# ETH_SWITCH.net
KiCad netlist of a schematic drawn in Altium Designer
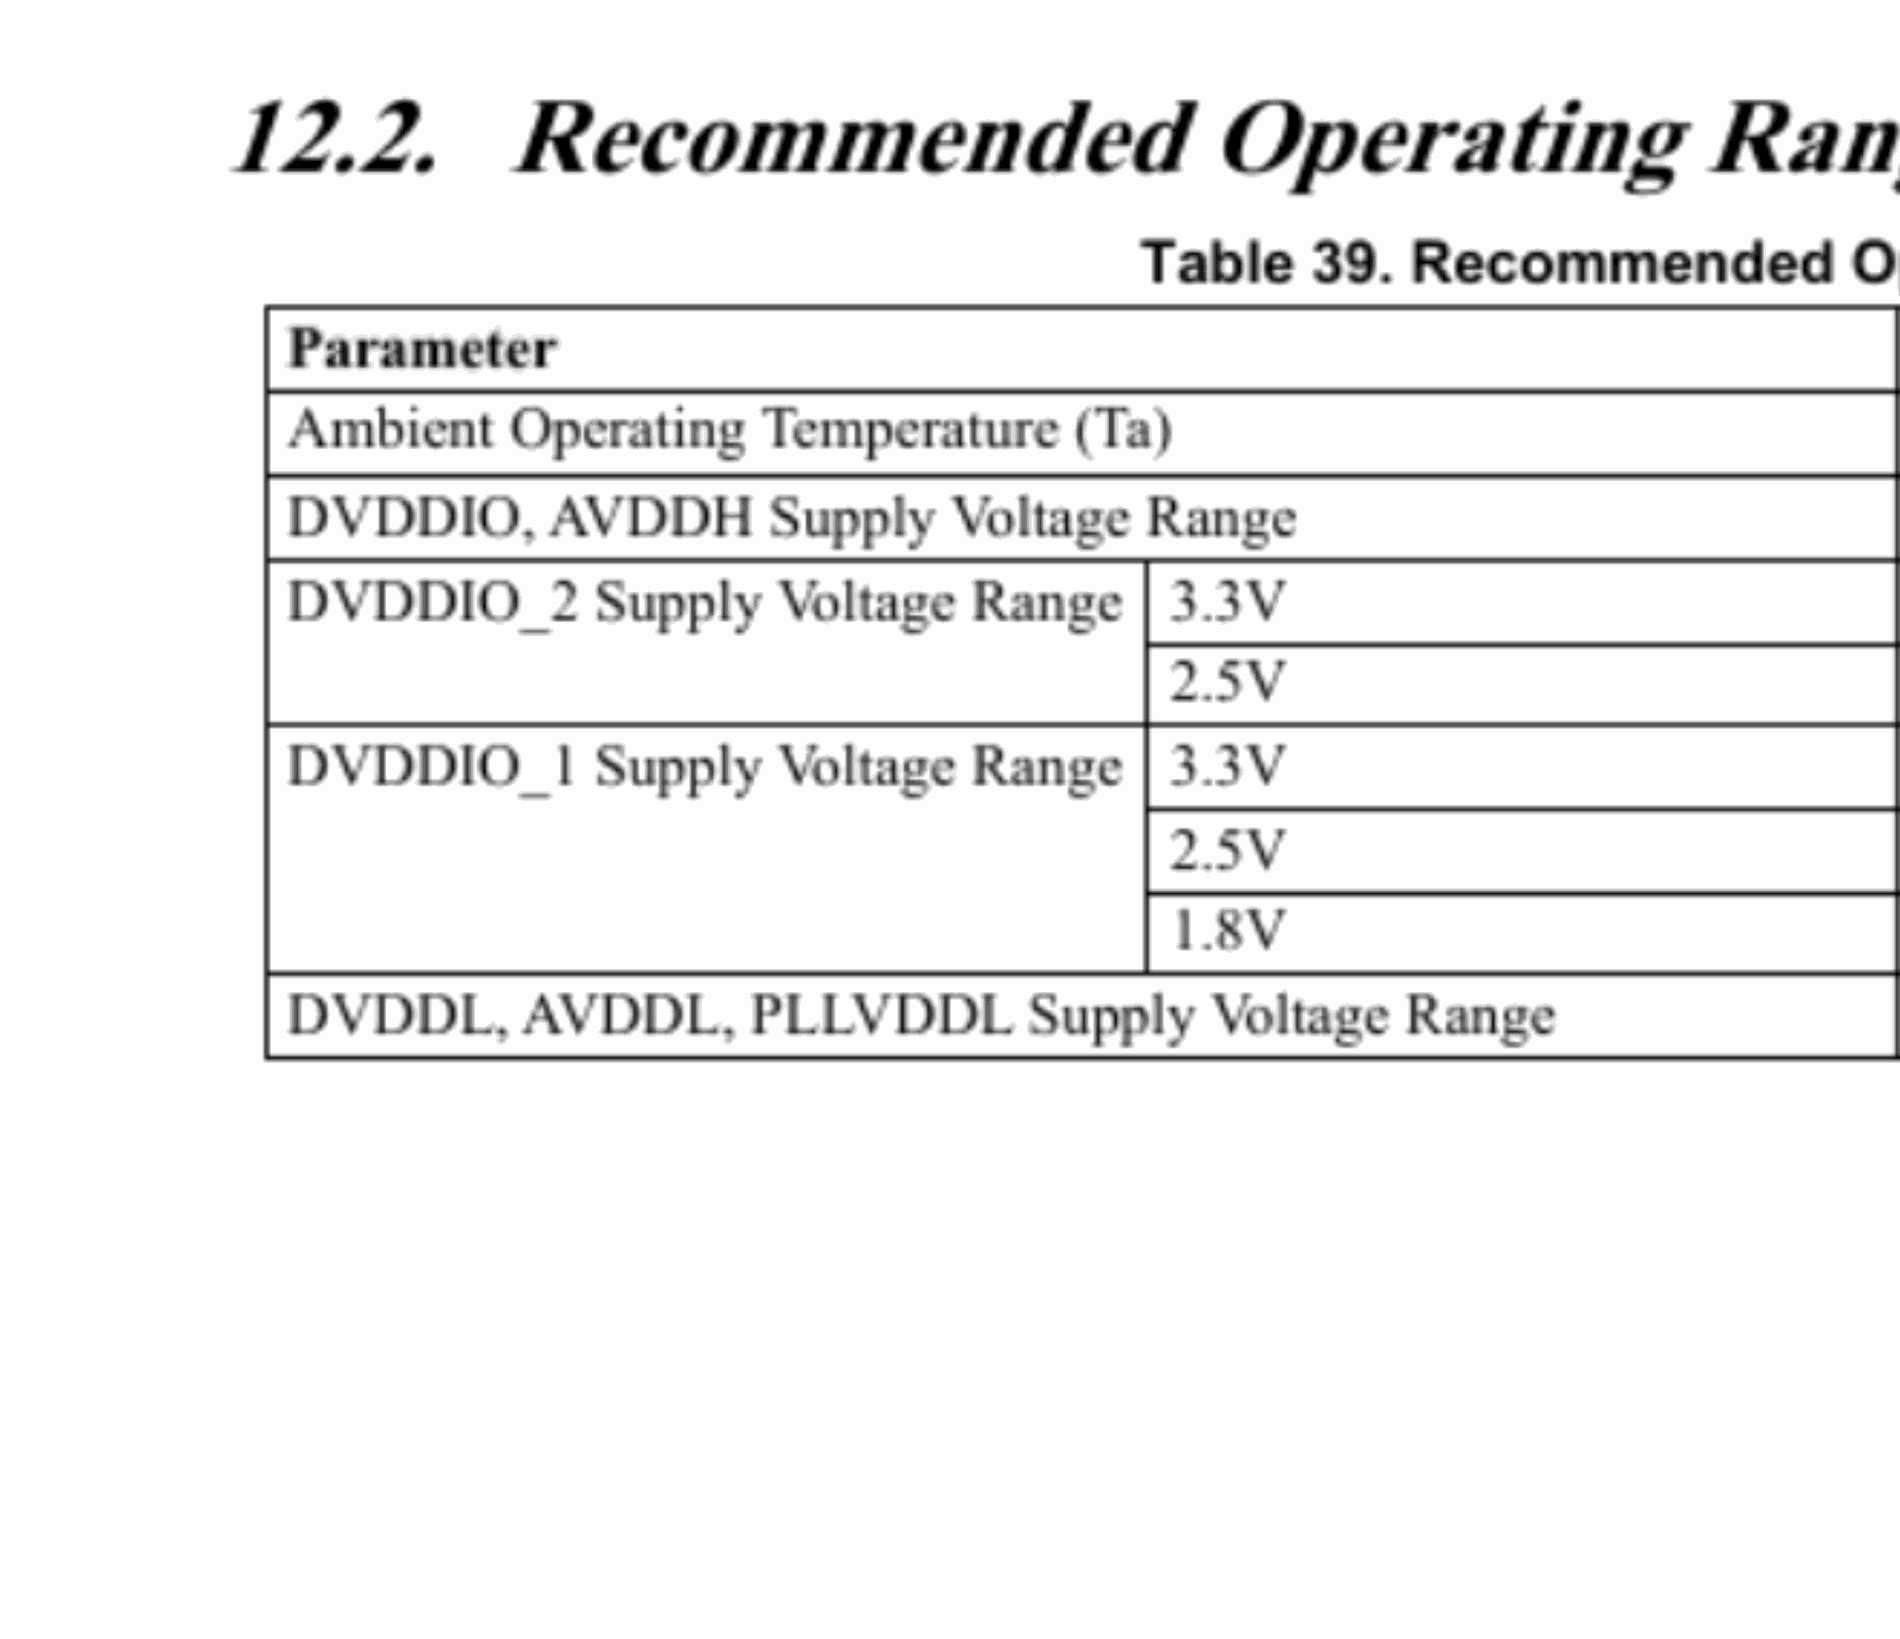
[diagram p0: ETH_SWITCH.SchDoc, top left]
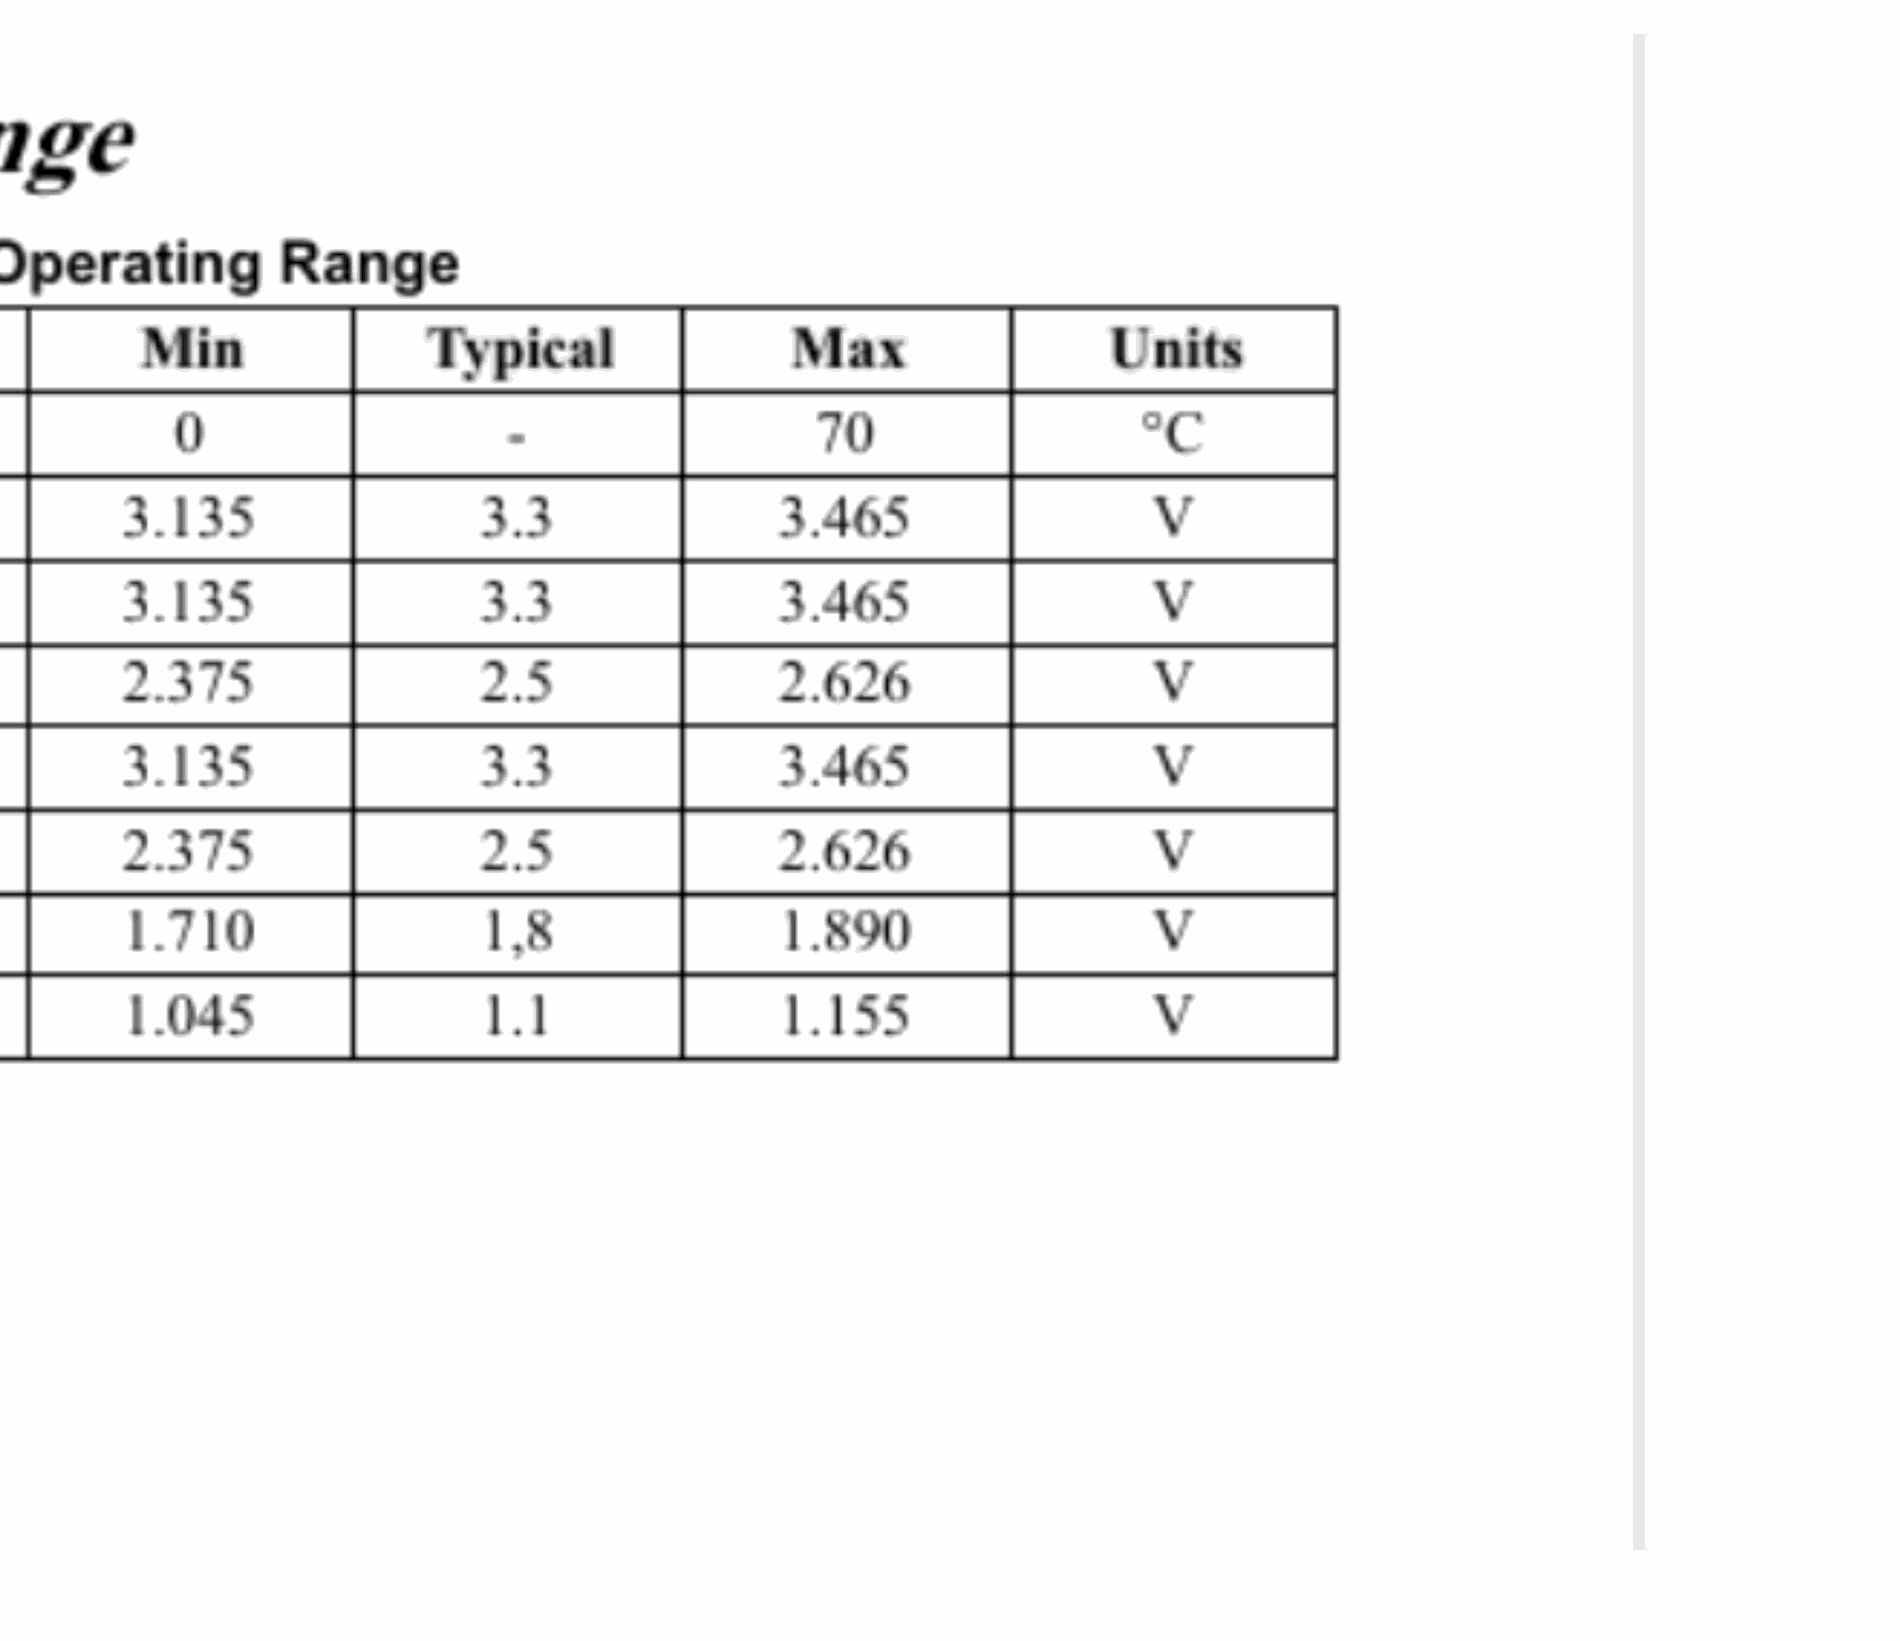
[diagram p1: ETH_SWITCH.SchDoc, top right]
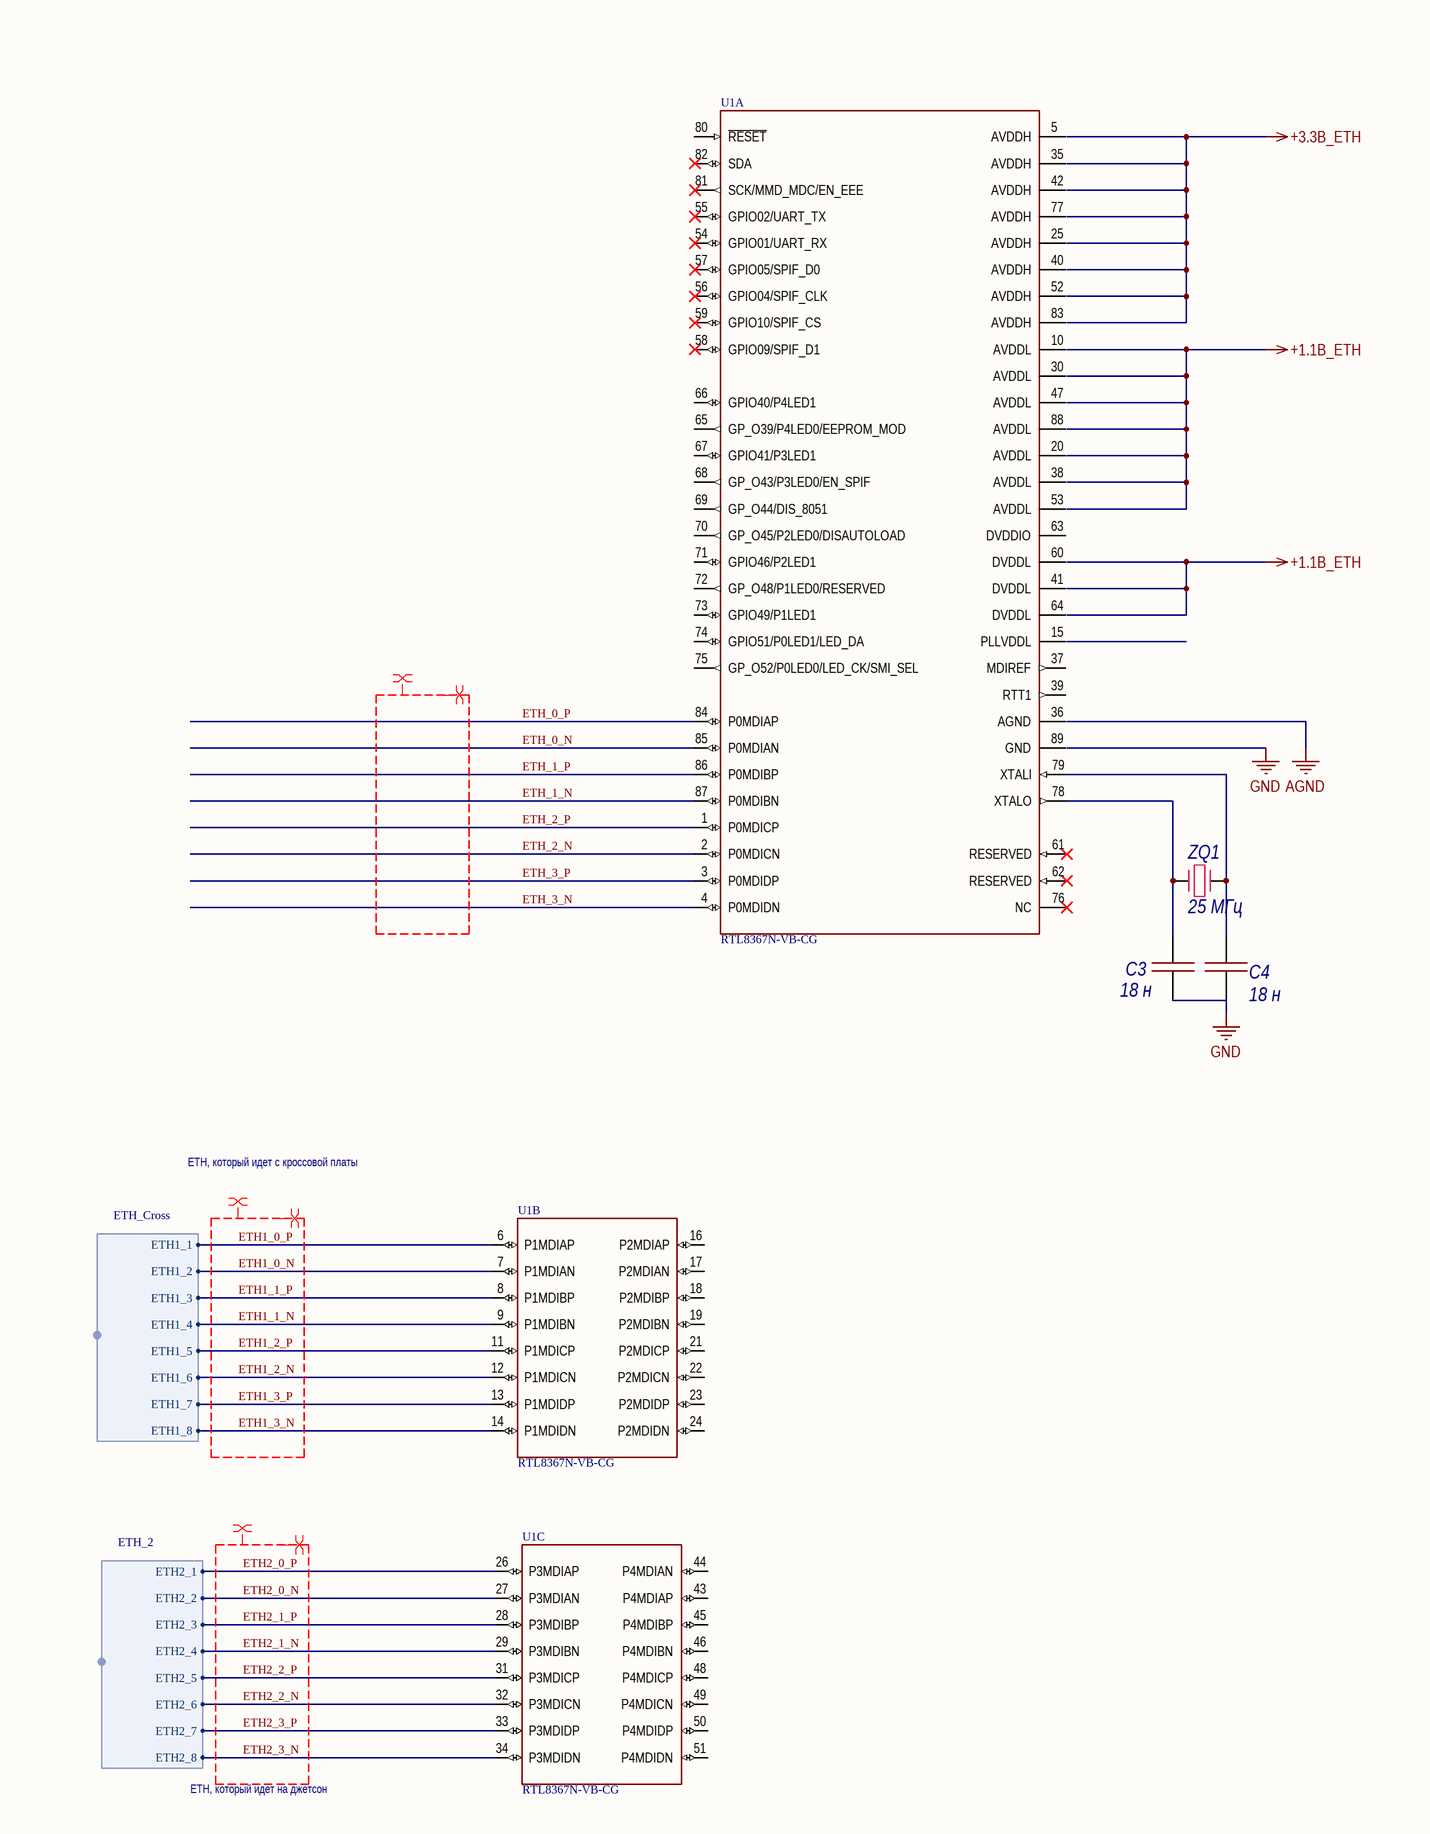
[diagram p2: ETH_SWITCH.SchDoc, bottom left]

(export (version "E")
  (design (tool "Eeschema 10.0.6"))
  (components
    (comp (ref "C3")
      (value "18 н")
      (footprint "0603C")
      (description "Конденсатор")
      (fields (field (name "PART NUMBER") "Capacitor_18n_10_50V_X7R_0603C") (field (name "TOLERANCE") "0,1"))
      (libsource (lib "Hydrolib") (part "Capacitor"))
    )
    (comp (ref "C4")
      (value "18 н")
      (footprint "0603C")
      (description "Конденсатор")
      (fields (field (name "PART NUMBER") "Capacitor_18n_10_50V_X7R_0603C") (field (name "TOLERANCE") "0,1"))
      (libsource (lib "Hydrolib") (part "Capacitor"))
    )
    (comp (ref "U1")
      (value "RTL8367N-VB-CG")
      (footprint "QFN40P1000X1000X90-89N")
      (fields (field (name "MF") "Realtek"))
      (libsource (lib "Hydrolib") (part "RTL8367N-VB-CG"))
    )
    (comp (ref "ZQ1")
      (value "25 МГц")
      (footprint "HC49SD")
      (description "Кварцевый резонатор")
      (fields (field (name "PART NUMBER") "XTAL"))
      (libsource (lib "Hydrolib") (part "XTAL"))
    )
  )
  (nets
    (net (code "3") (name "/ETH1_0_N") (class "Default")
      (node (ref "U1") (pin "7") (pinfunction "P1MDIAN_7") (pintype "bidirectional"))
    )
    (net (code "4") (name "/ETH1_0_P") (class "Default")
      (node (ref "U1") (pin "6") (pinfunction "P1MDIAP_6") (pintype "bidirectional"))
    )
    (net (code "5") (name "/ETH1_1_N") (class "Default")
      (node (ref "U1") (pin "9") (pinfunction "P1MDIBN_9") (pintype "bidirectional"))
    )
    (net (code "6") (name "/ETH1_1_P") (class "Default")
      (node (ref "U1") (pin "8") (pinfunction "P1MDIBP_8") (pintype "bidirectional"))
    )
    (net (code "7") (name "/ETH1_2_N") (class "Default")
      (node (ref "U1") (pin "12") (pinfunction "P1MDICN_12") (pintype "bidirectional"))
    )
    (net (code "8") (name "/ETH1_2_P") (class "Default")
      (node (ref "U1") (pin "11") (pinfunction "P1MDICP_11") (pintype "bidirectional"))
    )
    (net (code "9") (name "/ETH1_3_N") (class "Default")
      (node (ref "U1") (pin "14") (pinfunction "P1MDIDN_14") (pintype "bidirectional"))
    )
    (net (code "10") (name "/ETH1_3_P") (class "Default")
      (node (ref "U1") (pin "13") (pinfunction "P1MDIDP_13") (pintype "bidirectional"))
    )
    (net (code "11") (name "/ETH2_0_N") (class "Default")
      (node (ref "U1") (pin "27") (pinfunction "P3MDIAN_27") (pintype "bidirectional"))
    )
    (net (code "12") (name "/ETH2_0_P") (class "Default")
      (node (ref "U1") (pin "26") (pinfunction "P3MDIAP_26") (pintype "bidirectional"))
    )
    (net (code "13") (name "/ETH2_1_N") (class "Default")
      (node (ref "U1") (pin "29") (pinfunction "P3MDIBN_29") (pintype "bidirectional"))
    )
    (net (code "14") (name "/ETH2_1_P") (class "Default")
      (node (ref "U1") (pin "28") (pinfunction "P3MDIBP_28") (pintype "bidirectional"))
    )
    (net (code "15") (name "/ETH2_2_N") (class "Default")
      (node (ref "U1") (pin "32") (pinfunction "P3MDICN_32") (pintype "bidirectional"))
    )
    (net (code "16") (name "/ETH2_2_P") (class "Default")
      (node (ref "U1") (pin "31") (pinfunction "P3MDICP_31") (pintype "bidirectional"))
    )
    (net (code "17") (name "/ETH2_3_N") (class "Default")
      (node (ref "U1") (pin "34") (pinfunction "P3MDIDN_34") (pintype "bidirectional"))
    )
    (net (code "18") (name "/ETH2_3_P") (class "Default")
      (node (ref "U1") (pin "33") (pinfunction "P3MDIDP_33") (pintype "bidirectional"))
    )
    (net (code "19") (name "/ETH_0_N") (class "Default")
      (node (ref "U1") (pin "85") (pinfunction "P0MDIAN_85") (pintype "bidirectional"))
    )
    (net (code "20") (name "/ETH_0_P") (class "Default")
      (node (ref "U1") (pin "84") (pinfunction "P0MDIAP_84") (pintype "bidirectional"))
    )
    (net (code "21") (name "/ETH_1_N") (class "Default")
      (node (ref "U1") (pin "87") (pinfunction "P0MDIBN_87") (pintype "bidirectional"))
    )
    (net (code "22") (name "/ETH_1_P") (class "Default")
      (node (ref "U1") (pin "86") (pinfunction "P0MDIBP_86") (pintype "bidirectional"))
    )
    (net (code "23") (name "/ETH_2_N") (class "Default")
      (node (ref "U1") (pin "2") (pinfunction "P0MDICN_2") (pintype "bidirectional"))
    )
    (net (code "24") (name "/ETH_2_P") (class "Default")
      (node (ref "U1") (pin "1") (pinfunction "P0MDICP_1") (pintype "bidirectional"))
    )
    (net (code "25") (name "/ETH_3_N") (class "Default")
      (node (ref "U1") (pin "4") (pinfunction "P0MDIDN_4") (pintype "bidirectional"))
    )
    (net (code "26") (name "/ETH_3_P") (class "Default")
      (node (ref "U1") (pin "3") (pinfunction "P0MDIDP_3") (pintype "bidirectional"))
    )
    (net (code "28") (name "GND") (class "Default")
      (node (ref "C3") (pin "1") (pinfunction "1_1") (pintype "passive"))
      (node (ref "C4") (pin "2") (pinfunction "2_2") (pintype "passive"))
    )
    (net (code "29") (name "Net-(U1A-XTALI)") (class "Default")
      (node (ref "C4") (pin "1") (pinfunction "1_1") (pintype "passive"))
      (node (ref "U1") (pin "79") (pinfunction "XTALI_79") (pintype "input"))
      (node (ref "ZQ1") (pin "2") (pinfunction "2_2") (pintype "passive"))
    )
    (net (code "30") (name "Net-(U1A-XTALO)") (class "Default")
      (node (ref "C3") (pin "2") (pinfunction "2_2") (pintype "passive"))
      (node (ref "U1") (pin "78") (pinfunction "XTALO_78") (pintype "output"))
      (node (ref "ZQ1") (pin "1") (pinfunction "1_1") (pintype "passive"))
    )
    (net (code "31") (name "unconnected-(U1A-AGND-Pad36)") (class "Default")
      (node (ref "U1") (pin "36") (pinfunction "AGND_36") (pintype "power_in"))
    )
    (net (code "32") (name "unconnected-(U1A-AVDDH-Pad5)") (class "Default")
      (node (ref "U1") (pin "5") (pinfunction "AVDDH_5") (pintype "power_in"))
    )
    (net (code "33") (name "unconnected-(U1A-AVDDH-Pad25)") (class "Default")
      (node (ref "U1") (pin "25") (pinfunction "AVDDH_25") (pintype "power_in"))
    )
    (net (code "34") (name "unconnected-(U1A-AVDDH-Pad35)") (class "Default")
      (node (ref "U1") (pin "35") (pinfunction "AVDDH_35") (pintype "power_in"))
    )
    (net (code "35") (name "unconnected-(U1A-AVDDH-Pad40)") (class "Default")
      (node (ref "U1") (pin "40") (pinfunction "AVDDH_40") (pintype "power_in"))
    )
    (net (code "36") (name "unconnected-(U1A-AVDDH-Pad42)") (class "Default")
      (node (ref "U1") (pin "42") (pinfunction "AVDDH_42") (pintype "power_in"))
    )
    (net (code "37") (name "unconnected-(U1A-AVDDH-Pad52)") (class "Default")
      (node (ref "U1") (pin "52") (pinfunction "AVDDH_52") (pintype "power_in"))
    )
    (net (code "38") (name "unconnected-(U1A-AVDDH-Pad77)") (class "Default")
      (node (ref "U1") (pin "77") (pinfunction "AVDDH_77") (pintype "power_in"))
    )
    (net (code "39") (name "unconnected-(U1A-AVDDH-Pad83)") (class "Default")
      (node (ref "U1") (pin "83") (pinfunction "AVDDH_83") (pintype "power_in"))
    )
    (net (code "40") (name "unconnected-(U1A-AVDDL-Pad10)") (class "Default")
      (node (ref "U1") (pin "10") (pinfunction "AVDDL_10") (pintype "power_in"))
    )
    (net (code "41") (name "unconnected-(U1A-AVDDL-Pad20)") (class "Default")
      (node (ref "U1") (pin "20") (pinfunction "AVDDL_20") (pintype "power_in"))
    )
    (net (code "42") (name "unconnected-(U1A-AVDDL-Pad30)") (class "Default")
      (node (ref "U1") (pin "30") (pinfunction "AVDDL_30") (pintype "power_in"))
    )
    (net (code "43") (name "unconnected-(U1A-AVDDL-Pad38)") (class "Default")
      (node (ref "U1") (pin "38") (pinfunction "AVDDL_38") (pintype "power_in"))
    )
    (net (code "44") (name "unconnected-(U1A-AVDDL-Pad47)") (class "Default")
      (node (ref "U1") (pin "47") (pinfunction "AVDDL_47") (pintype "power_in"))
    )
    (net (code "45") (name "unconnected-(U1A-AVDDL-Pad53)") (class "Default")
      (node (ref "U1") (pin "53") (pinfunction "AVDDL_53") (pintype "power_in"))
    )
    (net (code "46") (name "unconnected-(U1A-AVDDL-Pad88)") (class "Default")
      (node (ref "U1") (pin "88") (pinfunction "AVDDL_88") (pintype "power_in"))
    )
    (net (code "47") (name "unconnected-(U1A-DVDDIO-Pad63)") (class "Default")
      (node (ref "U1") (pin "63") (pinfunction "DVDDIO_63") (pintype "power_in"))
    )
    (net (code "48") (name "unconnected-(U1A-DVDDL-Pad41)") (class "Default")
      (node (ref "U1") (pin "41") (pinfunction "DVDDL_41") (pintype "power_in"))
    )
    (net (code "49") (name "unconnected-(U1A-DVDDL-Pad60)") (class "Default")
      (node (ref "U1") (pin "60") (pinfunction "DVDDL_60") (pintype "power_in"))
    )
    (net (code "50") (name "unconnected-(U1A-DVDDL-Pad64)") (class "Default")
      (node (ref "U1") (pin "64") (pinfunction "DVDDL_64") (pintype "power_in"))
    )
    (net (code "51") (name "unconnected-(U1A-GND-Pad89)") (class "Default")
      (node (ref "U1") (pin "89") (pinfunction "GND_89") (pintype "power_in"))
    )
    (net (code "52") (name "unconnected-(U1A-GPIO01{slash}UART_RX-Pad54)") (class "Default")
      (node (ref "U1") (pin "54") (pinfunction "GPIO01/UART_RX_54") (pintype "bidirectional"))
    )
    (net (code "53") (name "unconnected-(U1A-GPIO02{slash}UART_TX-Pad55)") (class "Default")
      (node (ref "U1") (pin "55") (pinfunction "GPIO02/UART_TX_55") (pintype "bidirectional"))
    )
    (net (code "54") (name "unconnected-(U1A-GPIO04{slash}SPIF_CLK-Pad56)") (class "Default")
      (node (ref "U1") (pin "56") (pinfunction "GPIO04/SPIF_CLK_56") (pintype "bidirectional"))
    )
    (net (code "55") (name "unconnected-(U1A-GPIO05{slash}SPIF_D0-Pad57)") (class "Default")
      (node (ref "U1") (pin "57") (pinfunction "GPIO05/SPIF_D0_57") (pintype "bidirectional"))
    )
    (net (code "56") (name "unconnected-(U1A-GPIO09{slash}SPIF_D1-Pad58)") (class "Default")
      (node (ref "U1") (pin "58") (pinfunction "GPIO09/SPIF_D1_58") (pintype "bidirectional"))
    )
    (net (code "57") (name "unconnected-(U1A-GPIO10{slash}SPIF_CS-Pad59)") (class "Default")
      (node (ref "U1") (pin "59") (pinfunction "GPIO10/SPIF_CS_59") (pintype "bidirectional"))
    )
    (net (code "58") (name "unconnected-(U1A-GPIO40{slash}P4LED1-Pad66)") (class "Default")
      (node (ref "U1") (pin "66") (pinfunction "GPIO40/P4LED1_66") (pintype "bidirectional"))
    )
    (net (code "59") (name "unconnected-(U1A-GPIO41{slash}P3LED1-Pad67)") (class "Default")
      (node (ref "U1") (pin "67") (pinfunction "GPIO41/P3LED1_67") (pintype "bidirectional"))
    )
    (net (code "60") (name "unconnected-(U1A-GPIO46{slash}P2LED1-Pad71)") (class "Default")
      (node (ref "U1") (pin "71") (pinfunction "GPIO46/P2LED1_71") (pintype "bidirectional"))
    )
    (net (code "61") (name "unconnected-(U1A-GPIO49{slash}P1LED1-Pad73)") (class "Default")
      (node (ref "U1") (pin "73") (pinfunction "GPIO49/P1LED1_73") (pintype "bidirectional"))
    )
    (net (code "62") (name "unconnected-(U1A-GPIO51{slash}P0LED1{slash}LED_DA-Pad74)") (class "Default")
      (node (ref "U1") (pin "74") (pinfunction "GPIO51/P0LED1/LED_DA_74") (pintype "bidirectional"))
    )
    (net (code "63") (name "unconnected-(U1A-GP_O39{slash}P4LED0{slash}EEPROM_MOD-Pad65)") (class "Default")
      (node (ref "U1") (pin "65") (pinfunction "GP_O39/P4LED0/EEPROM_MOD_65") (pintype "output"))
    )
    (net (code "64") (name "unconnected-(U1A-GP_O43{slash}P3LED0{slash}EN_SPIF-Pad68)") (class "Default")
      (node (ref "U1") (pin "68") (pinfunction "GP_O43/P3LED0/EN_SPIF_68") (pintype "output"))
    )
    (net (code "65") (name "unconnected-(U1A-GP_O44{slash}DIS_8051-Pad69)") (class "Default")
      (node (ref "U1") (pin "69") (pinfunction "GP_O44/DIS_8051_69") (pintype "output"))
    )
    (net (code "66") (name "unconnected-(U1A-GP_O45{slash}P2LED0{slash}DISAUTOLOAD-Pad70)") (class "Default")
      (node (ref "U1") (pin "70") (pinfunction "GP_O45/P2LED0/DISAUTOLOAD_70") (pintype "output"))
    )
    (net (code "67") (name "unconnected-(U1A-GP_O48{slash}P1LED0{slash}RESERVED-Pad72)") (class "Default")
      (node (ref "U1") (pin "72") (pinfunction "GP_O48/P1LED0/RESERVED_72") (pintype "output"))
    )
    (net (code "68") (name "unconnected-(U1A-GP_O52{slash}P0LED0{slash}LED_CK{slash}SMI_SEL-Pad75)") (class "Default")
      (node (ref "U1") (pin "75") (pinfunction "GP_O52/P0LED0/LED_CK/SMI_SEL_75") (pintype "output"))
    )
    (net (code "69") (name "unconnected-(U1A-MDIREF-Pad37)") (class "Default")
      (node (ref "U1") (pin "37") (pinfunction "MDIREF_37") (pintype "output"))
    )
    (net (code "70") (name "unconnected-(U1A-NC-Pad76)") (class "Default")
      (node (ref "U1") (pin "76") (pinfunction "NC_76") (pintype "passive+no_connect"))
    )
    (net (code "71") (name "unconnected-(U1A-PLLVDDL-Pad15)") (class "Default")
      (node (ref "U1") (pin "15") (pinfunction "PLLVDDL_15") (pintype "power_in"))
    )
    (net (code "72") (name "unconnected-(U1A-RESERVED-Pad61)") (class "Default")
      (node (ref "U1") (pin "61") (pinfunction "RESERVED_61") (pintype "input+no_connect"))
    )
    (net (code "73") (name "unconnected-(U1A-RESERVED-Pad62)") (class "Default")
      (node (ref "U1") (pin "62") (pinfunction "RESERVED_62") (pintype "input+no_connect"))
    )
    (net (code "74") (name "unconnected-(U1A-RTT1-Pad39)") (class "Default")
      (node (ref "U1") (pin "39") (pinfunction "RTT1_39") (pintype "output"))
    )
    (net (code "75") (name "unconnected-(U1A-SCK{slash}MMD_MDC{slash}EN_EEE-Pad81)") (class "Default")
      (node (ref "U1") (pin "81") (pinfunction "SCK/MMD_MDC/EN_EEE_81") (pintype "output"))
    )
    (net (code "76") (name "unconnected-(U1A-SDA-Pad82)") (class "Default")
      (node (ref "U1") (pin "82") (pinfunction "SDA_82") (pintype "bidirectional"))
    )
    (net (code "77") (name "unconnected-(U1A-~{RESET}-Pad80)") (class "Default")
      (node (ref "U1") (pin "80") (pinfunction "~{RESET}_80") (pintype "input"))
    )
    (net (code "78") (name "unconnected-(U1B-P2MDIAN-Pad17)") (class "Default")
      (node (ref "U1") (pin "17") (pinfunction "P2MDIAN_17") (pintype "bidirectional"))
    )
    (net (code "79") (name "unconnected-(U1B-P2MDIAP-Pad16)") (class "Default")
      (node (ref "U1") (pin "16") (pinfunction "P2MDIAP_16") (pintype "bidirectional"))
    )
    (net (code "80") (name "unconnected-(U1B-P2MDIBN-Pad19)") (class "Default")
      (node (ref "U1") (pin "19") (pinfunction "P2MDIBN_19") (pintype "bidirectional"))
    )
    (net (code "81") (name "unconnected-(U1B-P2MDIBP-Pad18)") (class "Default")
      (node (ref "U1") (pin "18") (pinfunction "P2MDIBP_18") (pintype "bidirectional"))
    )
    (net (code "82") (name "unconnected-(U1B-P2MDICN-Pad22)") (class "Default")
      (node (ref "U1") (pin "22") (pinfunction "P2MDICN_22") (pintype "bidirectional"))
    )
    (net (code "83") (name "unconnected-(U1B-P2MDICP-Pad21)") (class "Default")
      (node (ref "U1") (pin "21") (pinfunction "P2MDICP_21") (pintype "bidirectional"))
    )
    (net (code "84") (name "unconnected-(U1B-P2MDIDN-Pad24)") (class "Default")
      (node (ref "U1") (pin "24") (pinfunction "P2MDIDN_24") (pintype "bidirectional"))
    )
    (net (code "85") (name "unconnected-(U1B-P2MDIDP-Pad23)") (class "Default")
      (node (ref "U1") (pin "23") (pinfunction "P2MDIDP_23") (pintype "bidirectional"))
    )
    (net (code "86") (name "unconnected-(U1C-P4MDIAN-Pad44)") (class "Default")
      (node (ref "U1") (pin "44") (pinfunction "P4MDIAN_44") (pintype "bidirectional"))
    )
    (net (code "87") (name "unconnected-(U1C-P4MDIAP-Pad43)") (class "Default")
      (node (ref "U1") (pin "43") (pinfunction "P4MDIAP_43") (pintype "bidirectional"))
    )
    (net (code "88") (name "unconnected-(U1C-P4MDIBN-Pad46)") (class "Default")
      (node (ref "U1") (pin "46") (pinfunction "P4MDIBN_46") (pintype "bidirectional"))
    )
    (net (code "89") (name "unconnected-(U1C-P4MDIBP-Pad45)") (class "Default")
      (node (ref "U1") (pin "45") (pinfunction "P4MDIBP_45") (pintype "bidirectional"))
    )
    (net (code "90") (name "unconnected-(U1C-P4MDICN-Pad49)") (class "Default")
      (node (ref "U1") (pin "49") (pinfunction "P4MDICN_49") (pintype "bidirectional"))
    )
    (net (code "91") (name "unconnected-(U1C-P4MDICP-Pad48)") (class "Default")
      (node (ref "U1") (pin "48") (pinfunction "P4MDICP_48") (pintype "bidirectional"))
    )
    (net (code "92") (name "unconnected-(U1C-P4MDIDN-Pad51)") (class "Default")
      (node (ref "U1") (pin "51") (pinfunction "P4MDIDN_51") (pintype "bidirectional"))
    )
    (net (code "93") (name "unconnected-(U1C-P4MDIDP-Pad50)") (class "Default")
      (node (ref "U1") (pin "50") (pinfunction "P4MDIDP_50") (pintype "bidirectional"))
    )
  )
)
